# attiny_shield.net
KiCad netlist of a schematic drawn in EAGLE
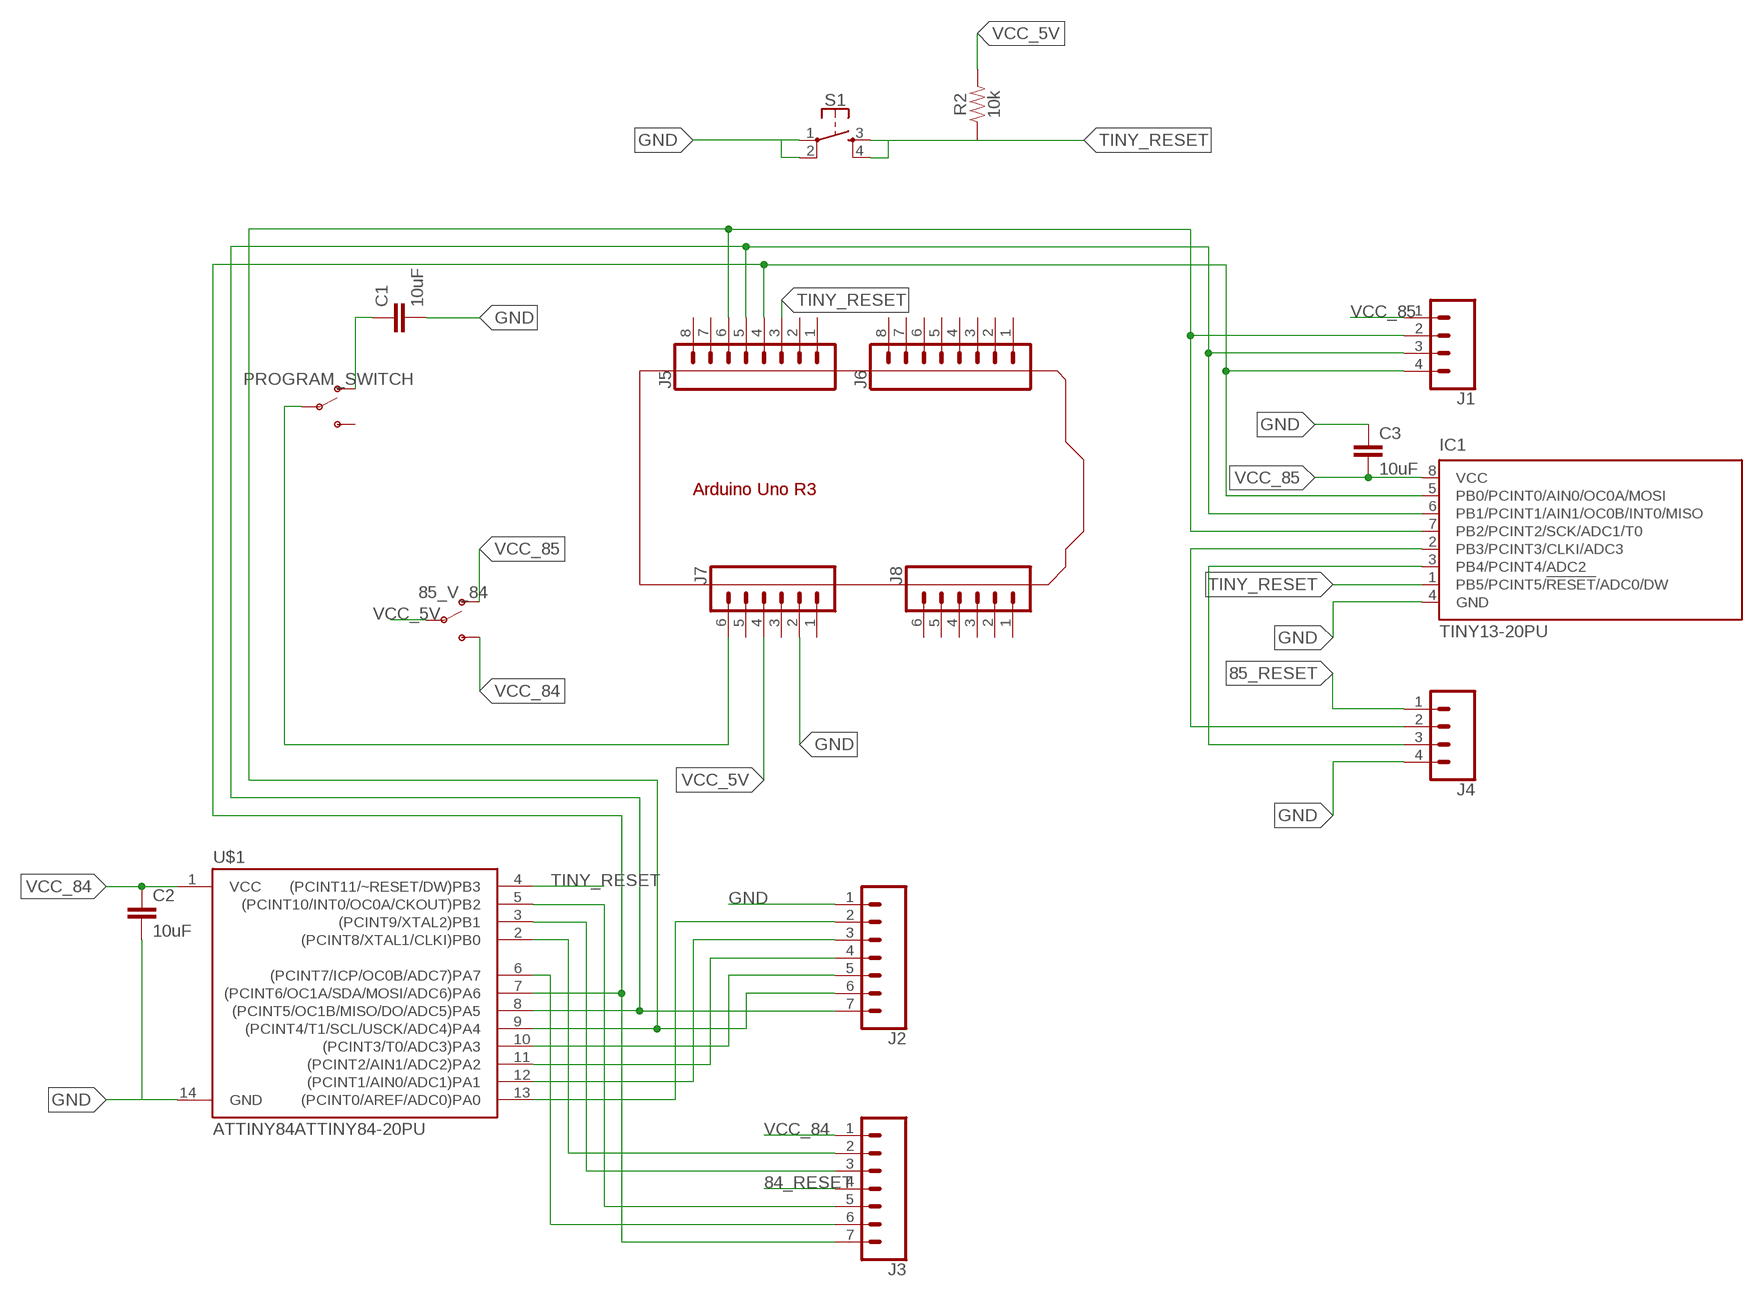
[diagram p0: schematic, sheet 1]

(export (version "E")
  (design (tool "Eeschema 10.0.6"))
  (components
    (comp (ref "85_V_84")
      (value "SPARKFUN-SWITCHES_SWITCH-SPDT-SMD-AYZ0202")
      (footprint "eagle-import:SPARKFUN-SWITCHES_SWITCH_DPDT_SMD_AYZ0202")
      (libsource (lib "eagle-import") (part "SPARKFUN-SWITCHES_SWITCH-SPDT-SMD-AYZ0202"))
    )
    (comp (ref "C1")
      (value "10uF")
      (footprint "eagle-import:0805")
      (libsource (lib "eagle-import") (part "10UF-0805-10V-10%"))
    )
    (comp (ref "C2")
      (value "10uF")
      (footprint "eagle-import:0805")
      (libsource (lib "eagle-import") (part "10UF-0805-10V-10%"))
    )
    (comp (ref "C3")
      (value "10uF")
      (footprint "eagle-import:0805")
      (libsource (lib "eagle-import") (part "10UF-0805-10V-10%"))
    )
    (comp (ref "IC1")
      (value "TINY13-20PU")
      (footprint "eagle-import:DIL08")
      (fields (field (name "MPN") "ATTINY13-20PU"))
      (libsource (lib "eagle-import") (part "TINY13PU-20"))
    )
    (comp (ref "J1")
      (value "CONN_04")
      (footprint "eagle-import:1X04")
      (libsource (lib "eagle-import") (part "CONN_04"))
    )
    (comp (ref "J2")
      (value "CONN_07")
      (footprint "eagle-import:1X07")
      (libsource (lib "eagle-import") (part "CONN_07"))
    )
    (comp (ref "J3")
      (value "CONN_07")
      (footprint "eagle-import:1X07")
      (libsource (lib "eagle-import") (part "CONN_07"))
    )
    (comp (ref "J4")
      (value "CONN_04")
      (footprint "eagle-import:1X04")
      (libsource (lib "eagle-import") (part "CONN_04"))
    )
    (comp (ref "J5")
      (value "CONN_08\"")
      (footprint "eagle-import:1X08")
      (libsource (lib "eagle-import") (part "CONN_08{dblquote}"))
    )
    (comp (ref "J6")
      (value "CONN_08\"")
      (footprint "eagle-import:1X08")
      (libsource (lib "eagle-import") (part "CONN_08{dblquote}"))
    )
    (comp (ref "J7")
      (value "CONN_06SILK_FEMALE_PTH")
      (footprint "eagle-import:1X06")
      (libsource (lib "eagle-import") (part "CONN_06SILK_FEMALE_PTH"))
    )
    (comp (ref "J8")
      (value "CONN_06SILK_FEMALE_PTH")
      (footprint "eagle-import:1X06")
      (libsource (lib "eagle-import") (part "CONN_06SILK_FEMALE_PTH"))
    )
    (comp (ref "PROGRAM_SWITCH")
      (value "SWITCH-SPDT-SMD-AYZ0202")
      (footprint "eagle-import:SWITCH_DPDT_SMD_AYZ0202")
      (libsource (lib "eagle-import") (part "SWITCH-SPDT-SMD-AYZ0202"))
    )
    (comp (ref "R2")
      (value "10k")
      (footprint "eagle-import:SPARKFUN-RESISTORS_0603")
      (libsource (lib "eagle-import") (part "SPARKFUN-RESISTORS_10KOHM-0603-1/10W-1%"))
    )
    (comp (ref "S1")
      (value "SPARKFUN-SWITCHES_MOMENTARY-SWITCH-SPST-2-SMD-5.2MM")
      (footprint "eagle-import:SPARKFUN-SWITCHES_TACTILE_SWITCH_SMD_5.2MM")
      (libsource (lib "eagle-import") (part "SPARKFUN-SWITCHES_MOMENTARY-SWITCH-SPST-2-SMD-5.2MM"))
    )
    (comp (ref "U$1")
      (value "ATTINY84ATTINY84-20PU")
      (footprint "eagle-import:DIP14")
      (libsource (lib "eagle-import") (part "ATTINY84ATTINY84-20PU"))
    )
  )
  (nets
    (net (code "1") (name "/84_RESET") (class "Default")
      (node (ref "J3") (pin "4") (pinfunction "4_4") (pintype "passive"))
    )
    (net (code "2") (name "85_RESET") (class "Default")
      (node (ref "J4") (pin "1") (pinfunction "1_1") (pintype "passive"))
    )
    (net (code "3") (name "GND") (class "Default")
      (node (ref "C1") (pin "2") (pinfunction "2_2") (pintype "passive"))
      (node (ref "C2") (pin "2") (pinfunction "2_2") (pintype "passive"))
      (node (ref "C3") (pin "1") (pinfunction "1_1") (pintype "passive"))
      (node (ref "IC1") (pin "4") (pinfunction "GND_4") (pintype "power_in"))
      (node (ref "J2") (pin "1") (pinfunction "1_1") (pintype "passive"))
      (node (ref "J4") (pin "4") (pinfunction "4_4") (pintype "passive"))
      (node (ref "J7") (pin "2") (pinfunction "2_2") (pintype "passive"))
      (node (ref "S1") (pin "1") (pinfunction "1_1") (pintype "passive"))
      (node (ref "S1") (pin "2") (pinfunction "2_2") (pintype "passive"))
      (node (ref "U$1") (pin "14") (pinfunction "GND_14") (pintype "bidirectional"))
    )
    (net (code "4") (name "Net-(IC1-PB0{slash}PCINT0{slash}AIN0{slash}OC0A{slash}MOSI)") (class "Default")
      (node (ref "IC1") (pin "5") (pinfunction "PB0/PCINT0/AIN0/OC0A/MOSI_5") (pintype "bidirectional"))
      (node (ref "J1") (pin "4") (pinfunction "4_4") (pintype "passive"))
      (node (ref "J3") (pin "7") (pinfunction "7_7") (pintype "passive"))
      (node (ref "J5") (pin "4") (pinfunction "4_4") (pintype "passive"))
      (node (ref "U$1") (pin "7") (pinfunction "(PCINT6/OC1A/SDA/MOSI/ADC6)PA6_7") (pintype "bidirectional"))
    )
    (net (code "5") (name "Net-(IC1-PB1{slash}PCINT1{slash}AIN1{slash}OC0B{slash}INT0{slash}MISO)") (class "Default")
      (node (ref "IC1") (pin "6") (pinfunction "PB1/PCINT1/AIN1/OC0B/INT0/MISO_6") (pintype "bidirectional"))
      (node (ref "J1") (pin "3") (pinfunction "3_3") (pintype "passive"))
      (node (ref "J2") (pin "7") (pinfunction "7_7") (pintype "passive"))
      (node (ref "J5") (pin "5") (pinfunction "5_5") (pintype "passive"))
      (node (ref "U$1") (pin "8") (pinfunction "(PCINT5/OC1B/MISO/DO/ADC5)PA5_8") (pintype "bidirectional"))
    )
    (net (code "6") (name "Net-(IC1-PB2{slash}PCINT2{slash}SCK{slash}ADC1{slash}T0)") (class "Default")
      (node (ref "IC1") (pin "7") (pinfunction "PB2/PCINT2/SCK/ADC1/T0_7") (pintype "bidirectional"))
      (node (ref "J1") (pin "2") (pinfunction "2_2") (pintype "passive"))
      (node (ref "J2") (pin "6") (pinfunction "6_6") (pintype "passive"))
      (node (ref "J5") (pin "6") (pinfunction "6_6") (pintype "passive"))
      (node (ref "U$1") (pin "9") (pinfunction "(PCINT4/T1/SCL/USCK/ADC4)PA4_9") (pintype "bidirectional"))
    )
    (net (code "7") (name "Net-(IC1-PB3{slash}PCINT3{slash}CLKI{slash}ADC3)") (class "Default")
      (node (ref "IC1") (pin "2") (pinfunction "PB3/PCINT3/CLKI/ADC3_2") (pintype "bidirectional"))
      (node (ref "J4") (pin "2") (pinfunction "2_2") (pintype "passive"))
    )
    (net (code "8") (name "Net-(IC1-PB4{slash}PCINT4{slash}ADC2)") (class "Default")
      (node (ref "IC1") (pin "3") (pinfunction "PB4/PCINT4/ADC2_3") (pintype "bidirectional"))
      (node (ref "J4") (pin "3") (pinfunction "3_3") (pintype "passive"))
    )
    (net (code "9") (name "Net-(PROGRAM_SWITCH-O)") (class "Default")
      (node (ref "C1") (pin "1") (pinfunction "1_1") (pintype "passive"))
      (node (ref "PROGRAM_SWITCH") (pin "1") (pinfunction "O_1") (pintype "passive"))
    )
    (net (code "10") (name "Net-(PROGRAM_SWITCH-P)") (class "Default")
      (node (ref "J7") (pin "6") (pinfunction "6_6") (pintype "passive"))
      (node (ref "PROGRAM_SWITCH") (pin "2") (pinfunction "P_2") (pintype "passive"))
    )
    (net (code "11") (name "Net-(U$1-(PCINT0{slash}AREF{slash}ADC0)PA0)") (class "Default")
      (node (ref "J2") (pin "2") (pinfunction "2_2") (pintype "passive"))
      (node (ref "U$1") (pin "13") (pinfunction "(PCINT0/AREF/ADC0)PA0_13") (pintype "bidirectional"))
    )
    (net (code "12") (name "Net-(U$1-(PCINT1{slash}AIN0{slash}ADC1)PA1)") (class "Default")
      (node (ref "J2") (pin "3") (pinfunction "3_3") (pintype "passive"))
      (node (ref "U$1") (pin "12") (pinfunction "(PCINT1/AIN0/ADC1)PA1_12") (pintype "bidirectional"))
    )
    (net (code "13") (name "Net-(U$1-(PCINT2{slash}AIN1{slash}ADC2)PA2)") (class "Default")
      (node (ref "J2") (pin "4") (pinfunction "4_4") (pintype "passive"))
      (node (ref "U$1") (pin "11") (pinfunction "(PCINT2/AIN1/ADC2)PA2_11") (pintype "bidirectional"))
    )
    (net (code "14") (name "Net-(U$1-(PCINT3{slash}T0{slash}ADC3)PA3)") (class "Default")
      (node (ref "J2") (pin "5") (pinfunction "5_5") (pintype "passive"))
      (node (ref "U$1") (pin "10") (pinfunction "(PCINT3/T0/ADC3)PA3_10") (pintype "bidirectional"))
    )
    (net (code "15") (name "Net-(U$1-(PCINT7{slash}ICP{slash}OC0B{slash}ADC7)PA7)") (class "Default")
      (node (ref "J3") (pin "6") (pinfunction "6_6") (pintype "passive"))
      (node (ref "U$1") (pin "6") (pinfunction "(PCINT7/ICP/OC0B/ADC7)PA7_6") (pintype "bidirectional"))
    )
    (net (code "16") (name "Net-(U$1-(PCINT8{slash}XTAL1{slash}CLKI)PB0)") (class "Default")
      (node (ref "J3") (pin "2") (pinfunction "2_2") (pintype "passive"))
      (node (ref "U$1") (pin "2") (pinfunction "(PCINT8/XTAL1/CLKI)PB0_2") (pintype "bidirectional"))
    )
    (net (code "17") (name "Net-(U$1-(PCINT9{slash}XTAL2)PB1)") (class "Default")
      (node (ref "J3") (pin "3") (pinfunction "3_3") (pintype "passive"))
      (node (ref "U$1") (pin "3") (pinfunction "(PCINT9/XTAL2)PB1_3") (pintype "bidirectional"))
    )
    (net (code "18") (name "Net-(U$1-(PCINT10{slash}INT0{slash}OC0A{slash}CKOUT)PB2)") (class "Default")
      (node (ref "J3") (pin "5") (pinfunction "5_5") (pintype "passive"))
      (node (ref "U$1") (pin "5") (pinfunction "(PCINT10/INT0/OC0A/CKOUT)PB2_5") (pintype "bidirectional"))
    )
    (net (code "19") (name "TINY_RESET") (class "Default")
      (node (ref "IC1") (pin "1") (pinfunction "PB5/PCINT5/~{RESET}/ADC0/DW_1") (pintype "bidirectional"))
      (node (ref "J5") (pin "3") (pinfunction "3_3") (pintype "passive"))
      (node (ref "R2") (pin "1") (pinfunction "1_1") (pintype "passive"))
      (node (ref "S1") (pin "3") (pinfunction "3_3") (pintype "passive"))
      (node (ref "S1") (pin "4") (pinfunction "4_4") (pintype "passive"))
      (node (ref "U$1") (pin "4") (pinfunction "(PCINT11/~{RESET/DW})PB3_4") (pintype "bidirectional"))
    )
    (net (code "20") (name "VCC_5V") (class "Default")
      (node (ref "85_V_84") (pin "2") (pinfunction "P_2") (pintype "passive"))
      (node (ref "J7") (pin "4") (pinfunction "4_4") (pintype "passive"))
      (node (ref "R2") (pin "2") (pinfunction "2_2") (pintype "passive"))
    )
    (net (code "21") (name "VCC_84") (class "Default")
      (node (ref "85_V_84") (pin "3") (pinfunction "S_3") (pintype "passive"))
      (node (ref "C2") (pin "1") (pinfunction "1_1") (pintype "passive"))
      (node (ref "J3") (pin "1") (pinfunction "1_1") (pintype "passive"))
      (node (ref "U$1") (pin "1") (pinfunction "VCC_1") (pintype "bidirectional"))
    )
    (net (code "22") (name "VCC_85") (class "Default")
      (node (ref "85_V_84") (pin "1") (pinfunction "O_1") (pintype "passive"))
      (node (ref "C3") (pin "2") (pinfunction "2_2") (pintype "passive"))
      (node (ref "IC1") (pin "8") (pinfunction "VCC_8") (pintype "power_in"))
      (node (ref "J1") (pin "1") (pinfunction "1_1") (pintype "passive"))
    )
    (net (code "23") (name "unconnected-(J5-Pad1)") (class "Default")
      (node (ref "J5") (pin "1") (pinfunction "1_1") (pintype "passive"))
    )
    (net (code "24") (name "unconnected-(J5-Pad2)") (class "Default")
      (node (ref "J5") (pin "2") (pinfunction "2_2") (pintype "passive"))
    )
    (net (code "25") (name "unconnected-(J5-Pad7)") (class "Default")
      (node (ref "J5") (pin "7") (pinfunction "7_7") (pintype "passive"))
    )
    (net (code "26") (name "unconnected-(J5-Pad8)") (class "Default")
      (node (ref "J5") (pin "8") (pinfunction "8_8") (pintype "passive"))
    )
    (net (code "27") (name "unconnected-(J6-Pad1)") (class "Default")
      (node (ref "J6") (pin "1") (pinfunction "1_1") (pintype "passive"))
    )
    (net (code "28") (name "unconnected-(J6-Pad2)") (class "Default")
      (node (ref "J6") (pin "2") (pinfunction "2_2") (pintype "passive"))
    )
    (net (code "29") (name "unconnected-(J6-Pad3)") (class "Default")
      (node (ref "J6") (pin "3") (pinfunction "3_3") (pintype "passive"))
    )
    (net (code "30") (name "unconnected-(J6-Pad4)") (class "Default")
      (node (ref "J6") (pin "4") (pinfunction "4_4") (pintype "passive"))
    )
    (net (code "31") (name "unconnected-(J6-Pad5)") (class "Default")
      (node (ref "J6") (pin "5") (pinfunction "5_5") (pintype "passive"))
    )
    (net (code "32") (name "unconnected-(J6-Pad6)") (class "Default")
      (node (ref "J6") (pin "6") (pinfunction "6_6") (pintype "passive"))
    )
    (net (code "33") (name "unconnected-(J6-Pad7)") (class "Default")
      (node (ref "J6") (pin "7") (pinfunction "7_7") (pintype "passive"))
    )
    (net (code "34") (name "unconnected-(J6-Pad8)") (class "Default")
      (node (ref "J6") (pin "8") (pinfunction "8_8") (pintype "passive"))
    )
    (net (code "35") (name "unconnected-(J7-Pad1)") (class "Default")
      (node (ref "J7") (pin "1") (pinfunction "1_1") (pintype "passive"))
    )
    (net (code "36") (name "unconnected-(J7-Pad3)") (class "Default")
      (node (ref "J7") (pin "3") (pinfunction "3_3") (pintype "passive"))
    )
    (net (code "37") (name "unconnected-(J7-Pad5)") (class "Default")
      (node (ref "J7") (pin "5") (pinfunction "5_5") (pintype "passive"))
    )
    (net (code "38") (name "unconnected-(J8-Pad1)") (class "Default")
      (node (ref "J8") (pin "1") (pinfunction "1_1") (pintype "passive"))
    )
    (net (code "39") (name "unconnected-(J8-Pad2)") (class "Default")
      (node (ref "J8") (pin "2") (pinfunction "2_2") (pintype "passive"))
    )
    (net (code "40") (name "unconnected-(J8-Pad3)") (class "Default")
      (node (ref "J8") (pin "3") (pinfunction "3_3") (pintype "passive"))
    )
    (net (code "41") (name "unconnected-(J8-Pad4)") (class "Default")
      (node (ref "J8") (pin "4") (pinfunction "4_4") (pintype "passive"))
    )
    (net (code "42") (name "unconnected-(J8-Pad5)") (class "Default")
      (node (ref "J8") (pin "5") (pinfunction "5_5") (pintype "passive"))
    )
    (net (code "43") (name "unconnected-(J8-Pad6)") (class "Default")
      (node (ref "J8") (pin "6") (pinfunction "6_6") (pintype "passive"))
    )
    (net (code "44") (name "unconnected-(PROGRAM_SWITCH-S-Pad3)") (class "Default")
      (node (ref "PROGRAM_SWITCH") (pin "3") (pinfunction "S_3") (pintype "passive"))
    )
  )
)
